# Power.net
KiCad netlist of a schematic drawn in Altium Designer
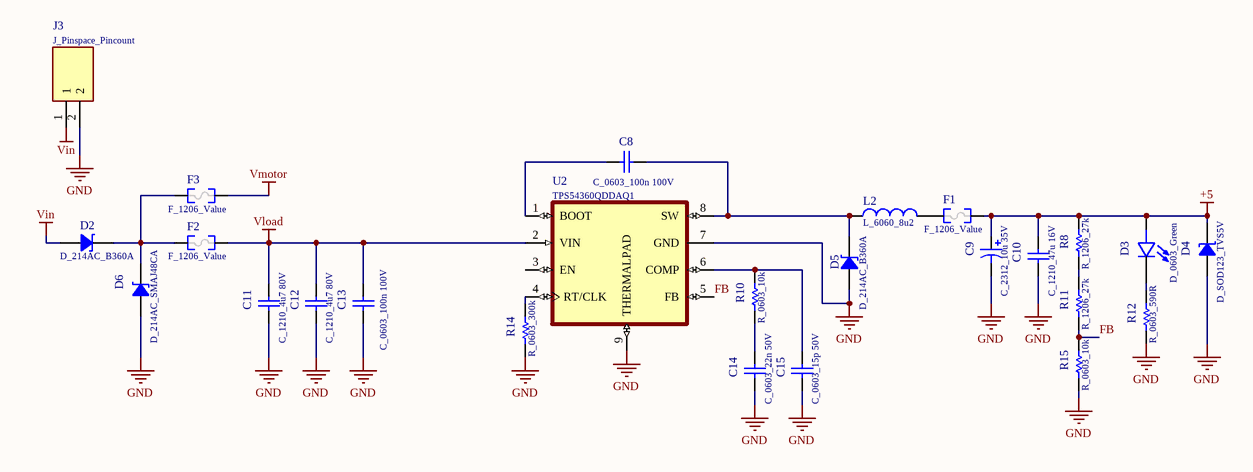
[diagram p0: Power.SchDoc]

(export (version "E")
  (design (tool "Eeschema 10.0.6"))
  (components
    (comp (ref "C8")
      (value "C_0603_100n 100V")
      (footprint "CAP 0603")
      (description "Capacitor")
      (fields (field (name "PUBLISHER") "Altium Limited"))
      (libsource (lib "HUE") (part "Cap"))
    )
    (comp (ref "C9")
      (value "C_2312_10u 35V")
      (footprint "CAP 2312 TAN")
      (description "Capacitor Tantalium")
      (fields (field (name "PUBLISHER") "Altium Limited"))
      (libsource (lib "HUE") (part "Cap Tantalium"))
    )
    (comp (ref "C10")
      (value "C_1210_47u 16V")
      (footprint "CAP 1210")
      (description "Capacitor")
      (fields (field (name "PUBLISHER") "Altium Limited"))
      (libsource (lib "HUE") (part "Cap"))
    )
    (comp (ref "C11")
      (value "C_1210_4u7 80V")
      (footprint "CAP 1210")
      (description "Capacitor")
      (fields (field (name "PUBLISHER") "Altium Limited"))
      (libsource (lib "HUE") (part "Cap"))
    )
    (comp (ref "C12")
      (value "C_1210_4u7 80V")
      (footprint "CAP 1210")
      (description "Capacitor")
      (fields (field (name "PUBLISHER") "Altium Limited"))
      (libsource (lib "HUE") (part "Cap"))
    )
    (comp (ref "C13")
      (value "C_0603_100n 100V")
      (footprint "CAP 0603")
      (description "Capacitor")
      (fields (field (name "PUBLISHER") "Altium Limited"))
      (libsource (lib "HUE") (part "Cap"))
    )
    (comp (ref "C14")
      (value "C_0603_22n 50V")
      (footprint "CAP 0603")
      (description "Capacitor")
      (fields (field (name "PUBLISHER") "Altium Limited"))
      (libsource (lib "HUE") (part "Cap"))
    )
    (comp (ref "C15")
      (value "C_0603_15p 50V")
      (footprint "CAP 0603")
      (description "Capacitor")
      (fields (field (name "PUBLISHER") "Altium Limited"))
      (libsource (lib "HUE") (part "Cap"))
    )
    (comp (ref "D2")
      (value "D_214AC_B360A")
      (footprint "DO214AC SMA")
      (description "Zener Diode")
      (libsource (lib "HUE") (part "Diode Zener"))
    )
    (comp (ref "D3")
      (value "D_0603_Green")
      (footprint "Led 0603")
      (description "Led")
      (fields (field (name "MP") "SML-D12FWT86") (field (name "MF") "Rohm"))
      (libsource (lib "HUE") (part "Led"))
    )
    (comp (ref "D4")
      (value "D_SOD123_TVS5V")
      (footprint "SOD-123")
      (description "Rectifier Diode")
      (libsource (lib "HUE") (part "DIODE TVS UNI"))
    )
    (comp (ref "D5")
      (value "D_214AC_B360A")
      (footprint "DO214AC SMA")
      (description "Zener Diode")
      (libsource (lib "HUE") (part "Diode Zener"))
    )
    (comp (ref "D6")
      (value "D_214AC_SMAJ48CA")
      (footprint "DO214AC SMA")
      (description "Zener Diode")
      (libsource (lib "HUE") (part "Diode Zener"))
    )
    (comp (ref "F1")
      (value "F_1206_Value")
      (footprint "FUSE 1206_3216 0.6MM")
      (libsource (lib "HUE") (part "Fuse"))
    )
    (comp (ref "F2")
      (value "F_1206_Value")
      (footprint "FUSE 1206_3216 0.6MM")
      (libsource (lib "HUE") (part "Fuse"))
    )
    (comp (ref "F3")
      (value "F_1206_Value")
      (footprint "FUSE 1206_3216 0.6MM")
      (libsource (lib "HUE") (part "Fuse"))
    )
    (comp (ref "J3")
      (value "J_Pinspace_Pincount")
      (footprint "2 Pin PCB STB 5.08")
      (fields (field (name "MF") "CUI Devices") (field (name "MP") "TBP02R1-381-02BE"))
      (libsource (lib "HUE") (part "2 Pin PCB Terminal Block"))
    )
    (comp (ref "L2")
      (value "L_6060_8u2")
      (footprint "Inductor 6060")
      (description "Inductor")
      (fields (field (name "PUBLISHER") "Altium Limited"))
      (libsource (lib "HUE") (part "Inductor"))
    )
    (comp (ref "R8")
      (value "R_1206_27k")
      (footprint "RES 1206")
      (description "Resistor")
      (fields (field (name "PUBLISHER") "Altium Limited"))
      (libsource (lib "HUE") (part "Res"))
    )
    (comp (ref "R10")
      (value "R_0603_10k")
      (footprint "RES 0603")
      (description "Resistor")
      (fields (field (name "PUBLISHER") "Altium Limited"))
      (libsource (lib "HUE") (part "Res"))
    )
    (comp (ref "R11")
      (value "R_1206_27k")
      (footprint "RES 1206")
      (description "Resistor")
      (fields (field (name "PUBLISHER") "Altium Limited"))
      (libsource (lib "HUE") (part "Res"))
    )
    (comp (ref "R12")
      (value "R_0603_590R")
      (footprint "RES 0603")
      (description "Resistor")
      (fields (field (name "PUBLISHER") "Altium Limited"))
      (libsource (lib "HUE") (part "Res"))
    )
    (comp (ref "R14")
      (value "R_0603_300k")
      (footprint "RES 0603")
      (description "Resistor")
      (fields (field (name "PUBLISHER") "Altium Limited"))
      (libsource (lib "HUE") (part "Res"))
    )
    (comp (ref "R15")
      (value "R_0603_10k")
      (footprint "RES 1206")
      (description "Resistor")
      (fields (field (name "PUBLISHER") "Altium Limited"))
      (libsource (lib "HUE") (part "Res"))
    )
    (comp (ref "U2")
      (value "TPS54360QDDAQ1")
      (footprint "SOIC8")
      (libsource (lib "HUE") (part "TPS54360QDDAQ1"))
    )
  )
  (nets
    (net (code "1") (name "+5") (class "Default")
      (node (ref "C10") (pin "1") (pinfunction "1_1") (pintype "passive"))
      (node (ref "C9") (pin "1") (pinfunction "1_1") (pintype "passive"))
      (node (ref "D3") (pin "1") (pinfunction "A_1") (pintype "passive"))
      (node (ref "D4") (pin "2") (pinfunction "2_2") (pintype "passive"))
      (node (ref "F1") (pin "2") (pinfunction "2_2") (pintype "passive"))
      (node (ref "R8") (pin "2") (pinfunction "2_2") (pintype "passive"))
    )
    (net (code "2") (name "/FB") (class "Default")
      (node (ref "R11") (pin "1") (pinfunction "1_1") (pintype "passive"))
      (node (ref "R15") (pin "2") (pinfunction "2_2") (pintype "passive"))
      (node (ref "U2") (pin "5") (pinfunction "FB_5") (pintype "bidirectional"))
    )
    (net (code "3") (name "GND") (class "Default")
      (node (ref "C10") (pin "2") (pinfunction "2_2") (pintype "passive"))
      (node (ref "C11") (pin "2") (pinfunction "2_2") (pintype "passive"))
      (node (ref "C12") (pin "2") (pinfunction "2_2") (pintype "passive"))
      (node (ref "C13") (pin "2") (pinfunction "2_2") (pintype "passive"))
      (node (ref "C14") (pin "2") (pinfunction "2_2") (pintype "passive"))
      (node (ref "C15") (pin "2") (pinfunction "2_2") (pintype "passive"))
      (node (ref "C9") (pin "2") (pinfunction "2_2") (pintype "passive"))
      (node (ref "D4") (pin "1") (pinfunction "1_1") (pintype "passive"))
      (node (ref "D5") (pin "1") (pinfunction "1_1") (pintype "passive"))
      (node (ref "D6") (pin "1") (pinfunction "1_1") (pintype "passive"))
      (node (ref "J3") (pin "2") (pinfunction "2_2") (pintype "passive"))
      (node (ref "R12") (pin "1") (pinfunction "1_1") (pintype "passive"))
      (node (ref "R14") (pin "1") (pinfunction "1_1") (pintype "passive"))
      (node (ref "R15") (pin "1") (pinfunction "1_1") (pintype "passive"))
      (node (ref "U2") (pin "7") (pinfunction "GND_7") (pintype "power_in"))
      (node (ref "U2") (pin "9") (pinfunction "THERMALPAD_9") (pintype "bidirectional"))
    )
    (net (code "4") (name "Net-(C14-Pad1)") (class "Default")
      (node (ref "C14") (pin "1") (pinfunction "1_1") (pintype "passive"))
      (node (ref "R10") (pin "1") (pinfunction "1_1") (pintype "passive"))
    )
    (net (code "5") (name "Net-(D2-Pad2)") (class "Default")
      (node (ref "D2") (pin "2") (pinfunction "2_2") (pintype "passive"))
      (node (ref "D6") (pin "2") (pinfunction "2_2") (pintype "passive"))
      (node (ref "F2") (pin "1") (pinfunction "1_1") (pintype "passive"))
      (node (ref "F3") (pin "1") (pinfunction "1_1") (pintype "passive"))
    )
    (net (code "6") (name "Net-(D3-C)") (class "Default")
      (node (ref "D3") (pin "2") (pinfunction "C_2") (pintype "passive"))
      (node (ref "R12") (pin "2") (pinfunction "2_2") (pintype "passive"))
    )
    (net (code "7") (name "Net-(F1-Pad1)") (class "Default")
      (node (ref "F1") (pin "1") (pinfunction "1_1") (pintype "passive"))
      (node (ref "L2") (pin "2") (pinfunction "2_2") (pintype "passive"))
    )
    (net (code "8") (name "Net-(R11-Pad2)") (class "Default")
      (node (ref "R11") (pin "2") (pinfunction "2_2") (pintype "passive"))
      (node (ref "R8") (pin "1") (pinfunction "1_1") (pintype "passive"))
    )
    (net (code "9") (name "Net-(U2-BOOT)") (class "Default")
      (node (ref "C8") (pin "2") (pinfunction "2_2") (pintype "passive"))
      (node (ref "U2") (pin "1") (pinfunction "BOOT_1") (pintype "bidirectional"))
    )
    (net (code "10") (name "Net-(U2-COMP)") (class "Default")
      (node (ref "C15") (pin "1") (pinfunction "1_1") (pintype "passive"))
      (node (ref "R10") (pin "2") (pinfunction "2_2") (pintype "passive"))
      (node (ref "U2") (pin "6") (pinfunction "COMP_6") (pintype "bidirectional"))
    )
    (net (code "11") (name "Net-(U2-RT{slash}CLK)") (class "Default")
      (node (ref "R14") (pin "2") (pinfunction "2_2") (pintype "passive"))
      (node (ref "U2") (pin "4") (pinfunction "RT/CLK_4") (pintype "bidirectional"))
    )
    (net (code "12") (name "Net-(U2-SW)") (class "Default")
      (node (ref "C8") (pin "1") (pinfunction "1_1") (pintype "passive"))
      (node (ref "D5") (pin "2") (pinfunction "2_2") (pintype "passive"))
      (node (ref "L2") (pin "1") (pinfunction "1_1") (pintype "passive"))
      (node (ref "U2") (pin "8") (pinfunction "SW_8") (pintype "bidirectional"))
    )
    (net (code "13") (name "Vin") (class "Default")
      (node (ref "D2") (pin "1") (pinfunction "1_1") (pintype "passive"))
      (node (ref "J3") (pin "1") (pinfunction "1_1") (pintype "passive"))
    )
    (net (code "14") (name "Vload") (class "Default")
      (node (ref "C11") (pin "1") (pinfunction "1_1") (pintype "passive"))
      (node (ref "C12") (pin "1") (pinfunction "1_1") (pintype "passive"))
      (node (ref "C13") (pin "1") (pinfunction "1_1") (pintype "passive"))
      (node (ref "F2") (pin "2") (pinfunction "2_2") (pintype "passive"))
      (node (ref "U2") (pin "2") (pinfunction "VIN_2") (pintype "input"))
    )
    (net (code "15") (name "Vmotor") (class "Default")
      (node (ref "F3") (pin "2") (pinfunction "2_2") (pintype "passive"))
    )
    (net (code "16") (name "unconnected-(U2-EN-Pad3)") (class "Default")
      (node (ref "U2") (pin "3") (pinfunction "EN_3") (pintype "bidirectional"))
    )
  )
)
